# Memory.net
KiCad netlist of a schematic drawn in Altium Designer
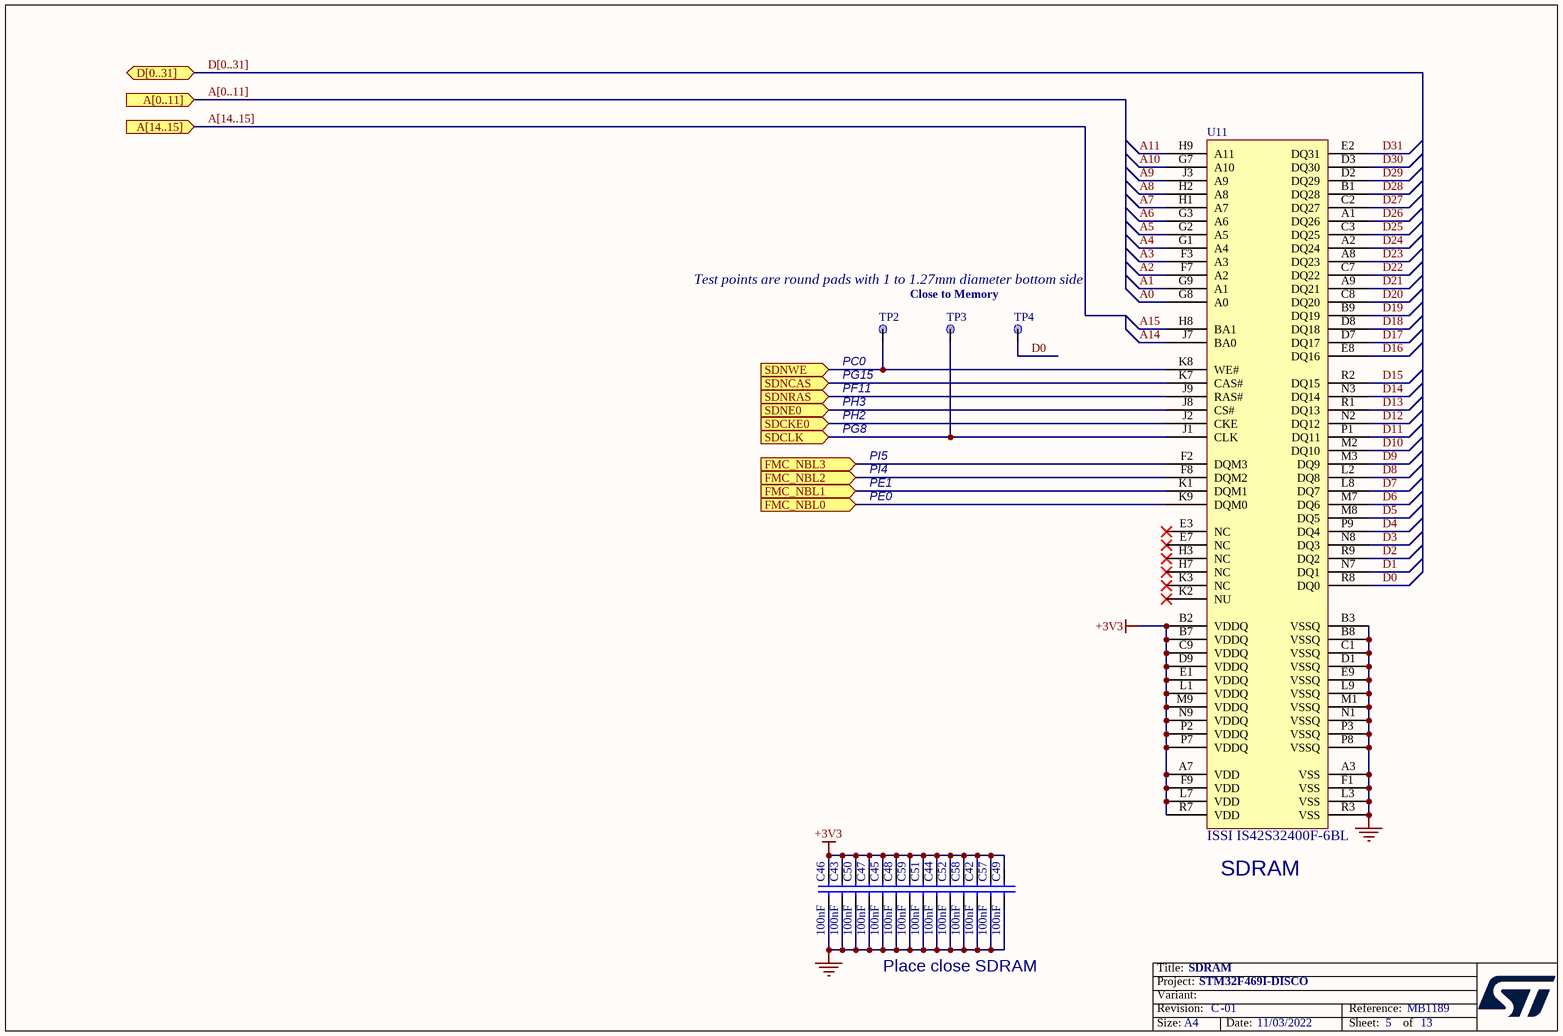
[diagram p0: Memory.SchDoc]

(export (version "E")
  (design (tool "Eeschema 10.0.6"))
  (components
    (comp (ref "C42")
      (value "100nF")
      (footprint "0402C")
      (description "Capacitor")
      (fields (field (name "PUBLISHER") "Altium Limited"))
      (libsource (lib "Miscellaneous Devices") (part "Cap"))
    )
    (comp (ref "C43")
      (value "100nF")
      (footprint "0402C")
      (description "Capacitor")
      (fields (field (name "PUBLISHER") "Altium Limited"))
      (libsource (lib "Miscellaneous Devices") (part "Cap"))
    )
    (comp (ref "C44")
      (value "100nF")
      (footprint "0402C")
      (description "Capacitor")
      (fields (field (name "PUBLISHER") "Altium Limited"))
      (libsource (lib "Miscellaneous Devices") (part "Cap"))
    )
    (comp (ref "C45")
      (value "100nF")
      (footprint "0402C")
      (description "Capacitor")
      (fields (field (name "PUBLISHER") "Altium Limited"))
      (libsource (lib "Miscellaneous Devices") (part "Cap"))
    )
    (comp (ref "C46")
      (value "100nF")
      (footprint "0402C")
      (description "Capacitor")
      (fields (field (name "PUBLISHER") "Altium Limited"))
      (libsource (lib "Miscellaneous Devices") (part "Cap"))
    )
    (comp (ref "C47")
      (value "100nF")
      (footprint "0402C")
      (description "Capacitor")
      (fields (field (name "PUBLISHER") "Altium Limited"))
      (libsource (lib "Miscellaneous Devices") (part "Cap"))
    )
    (comp (ref "C48")
      (value "100nF")
      (footprint "0402C")
      (description "Capacitor")
      (fields (field (name "PUBLISHER") "Altium Limited"))
      (libsource (lib "Miscellaneous Devices") (part "Cap"))
    )
    (comp (ref "C49")
      (value "100nF")
      (footprint "0402C")
      (description "Capacitor")
      (fields (field (name "PUBLISHER") "Altium Limited"))
      (libsource (lib "Miscellaneous Devices") (part "Cap"))
    )
    (comp (ref "C50")
      (value "100nF")
      (footprint "0402C")
      (description "Capacitor")
      (fields (field (name "PUBLISHER") "Altium Limited"))
      (libsource (lib "Miscellaneous Devices") (part "Cap"))
    )
    (comp (ref "C51")
      (value "100nF")
      (footprint "0402C")
      (description "Capacitor")
      (fields (field (name "PUBLISHER") "Altium Limited"))
      (libsource (lib "Miscellaneous Devices") (part "Cap"))
    )
    (comp (ref "C52")
      (value "100nF")
      (footprint "0402C")
      (description "Capacitor")
      (fields (field (name "PUBLISHER") "Altium Limited"))
      (libsource (lib "Miscellaneous Devices") (part "Cap"))
    )
    (comp (ref "C57")
      (value "100nF")
      (footprint "0402C")
      (description "Capacitor")
      (fields (field (name "PUBLISHER") "Altium Limited"))
      (libsource (lib "Miscellaneous Devices") (part "Cap"))
    )
    (comp (ref "C58")
      (value "100nF")
      (footprint "0402C")
      (description "Capacitor")
      (fields (field (name "PUBLISHER") "Altium Limited"))
      (libsource (lib "Miscellaneous Devices") (part "Cap"))
    )
    (comp (ref "C59")
      (value "100nF")
      (footprint "0402C")
      (description "Capacitor")
      (fields (field (name "PUBLISHER") "Altium Limited"))
      (libsource (lib "Miscellaneous Devices") (part "Cap"))
    )
    (comp (ref "TP2") (value "TP") (footprint "TP_C40") (libsource (lib "Almos") (part "TP")))
    (comp (ref "TP3") (value "TP") (footprint "TP_C40") (libsource (lib "Almos") (part "TP")))
    (comp (ref "TP4") (value "TP") (footprint "TP_C40") (libsource (lib "Almos") (part "TP")))
    (comp (ref "U11")
      (value "ISSI IS42S32400F-6BL")
      (footprint "ICC_VFBGA90_8X13_P080")
      (description "SDRAM 128MBit 166MHZ 90BGA")
      (libsource (lib "MB1189") (part "IS42S32400F-6BL"))
    )
  )
  (nets
    (net (code "1") (name "+3V3") (class "Default")
      (node (ref "C42") (pin "1") (pinfunction "1_1") (pintype "passive"))
      (node (ref "C43") (pin "1") (pinfunction "1_1") (pintype "passive"))
      (node (ref "C44") (pin "1") (pinfunction "1_1") (pintype "passive"))
      (node (ref "C45") (pin "1") (pinfunction "1_1") (pintype "passive"))
      (node (ref "C46") (pin "1") (pinfunction "1_1") (pintype "passive"))
      (node (ref "C47") (pin "1") (pinfunction "1_1") (pintype "passive"))
      (node (ref "C48") (pin "1") (pinfunction "1_1") (pintype "passive"))
      (node (ref "C49") (pin "1") (pinfunction "1_1") (pintype "passive"))
      (node (ref "C50") (pin "1") (pinfunction "1_1") (pintype "passive"))
      (node (ref "C51") (pin "1") (pinfunction "1_1") (pintype "passive"))
      (node (ref "C52") (pin "1") (pinfunction "1_1") (pintype "passive"))
      (node (ref "C57") (pin "1") (pinfunction "1_1") (pintype "passive"))
      (node (ref "C58") (pin "1") (pinfunction "1_1") (pintype "passive"))
      (node (ref "C59") (pin "1") (pinfunction "1_1") (pintype "passive"))
      (node (ref "U11") (pin "A7") (pinfunction "VDD_A7") (pintype "passive"))
      (node (ref "U11") (pin "B2") (pinfunction "VDDQ_B2") (pintype "passive"))
      (node (ref "U11") (pin "B7") (pinfunction "VDDQ_B7") (pintype "passive"))
      (node (ref "U11") (pin "C9") (pinfunction "VDDQ_C9") (pintype "passive"))
      (node (ref "U11") (pin "D9") (pinfunction "VDDQ_D9") (pintype "passive"))
      (node (ref "U11") (pin "E1") (pinfunction "VDDQ_E1") (pintype "passive"))
      (node (ref "U11") (pin "F9") (pinfunction "VDD_F9") (pintype "passive"))
      (node (ref "U11") (pin "L1") (pinfunction "VDDQ_L1") (pintype "passive"))
      (node (ref "U11") (pin "L7") (pinfunction "VDD_L7") (pintype "passive"))
      (node (ref "U11") (pin "M9") (pinfunction "VDDQ_M9") (pintype "passive"))
      (node (ref "U11") (pin "N9") (pinfunction "VDDQ_N9") (pintype "passive"))
      (node (ref "U11") (pin "P2") (pinfunction "VDDQ_P2") (pintype "passive"))
      (node (ref "U11") (pin "P7") (pinfunction "VDDQ_P7") (pintype "passive"))
      (node (ref "U11") (pin "R7") (pinfunction "VDD_R7") (pintype "passive"))
    )
    (net (code "2") (name "/A0") (class "Default")
      (node (ref "U11") (pin "G8") (pinfunction "A0_G8") (pintype "passive"))
    )
    (net (code "3") (name "/A1") (class "Default")
      (node (ref "U11") (pin "G9") (pinfunction "A1_G9") (pintype "passive"))
    )
    (net (code "4") (name "/A2") (class "Default")
      (node (ref "U11") (pin "F7") (pinfunction "A2_F7") (pintype "passive"))
    )
    (net (code "5") (name "/A3") (class "Default")
      (node (ref "U11") (pin "F3") (pinfunction "A3_F3") (pintype "passive"))
    )
    (net (code "6") (name "/A4") (class "Default")
      (node (ref "U11") (pin "G1") (pinfunction "A4_G1") (pintype "passive"))
    )
    (net (code "7") (name "/A5") (class "Default")
      (node (ref "U11") (pin "G2") (pinfunction "A5_G2") (pintype "passive"))
    )
    (net (code "8") (name "/A6") (class "Default")
      (node (ref "U11") (pin "G3") (pinfunction "A6_G3") (pintype "passive"))
    )
    (net (code "9") (name "/A7") (class "Default")
      (node (ref "U11") (pin "H1") (pinfunction "A7_H1") (pintype "passive"))
    )
    (net (code "10") (name "/A8") (class "Default")
      (node (ref "U11") (pin "H2") (pinfunction "A8_H2") (pintype "passive"))
    )
    (net (code "11") (name "/A9") (class "Default")
      (node (ref "U11") (pin "J3") (pinfunction "A9_J3") (pintype "passive"))
    )
    (net (code "12") (name "/A10") (class "Default")
      (node (ref "U11") (pin "G7") (pinfunction "A10_G7") (pintype "passive"))
    )
    (net (code "13") (name "/A11") (class "Default")
      (node (ref "U11") (pin "H9") (pinfunction "A11_H9") (pintype "passive"))
    )
    (net (code "14") (name "/A14") (class "Default")
      (node (ref "U11") (pin "J7") (pinfunction "BA0_J7") (pintype "passive"))
    )
    (net (code "15") (name "/A15") (class "Default")
      (node (ref "U11") (pin "H8") (pinfunction "BA1_H8") (pintype "passive"))
    )
    (net (code "18") (name "/D0") (class "Default")
      (node (ref "TP4") (pin "1") (pinfunction "1_1") (pintype "passive"))
      (node (ref "U11") (pin "R8") (pinfunction "DQ0_R8") (pintype "passive"))
    )
    (net (code "19") (name "/D1") (class "Default")
      (node (ref "U11") (pin "N7") (pinfunction "DQ1_N7") (pintype "passive"))
    )
    (net (code "20") (name "/D2") (class "Default")
      (node (ref "U11") (pin "R9") (pinfunction "DQ2_R9") (pintype "passive"))
    )
    (net (code "21") (name "/D3") (class "Default")
      (node (ref "U11") (pin "N8") (pinfunction "DQ3_N8") (pintype "passive"))
    )
    (net (code "22") (name "/D4") (class "Default")
      (node (ref "U11") (pin "P9") (pinfunction "DQ4_P9") (pintype "passive"))
    )
    (net (code "23") (name "/D5") (class "Default")
      (node (ref "U11") (pin "M8") (pinfunction "DQ5_M8") (pintype "passive"))
    )
    (net (code "24") (name "/D6") (class "Default")
      (node (ref "U11") (pin "M7") (pinfunction "DQ6_M7") (pintype "passive"))
    )
    (net (code "25") (name "/D7") (class "Default")
      (node (ref "U11") (pin "L8") (pinfunction "DQ7_L8") (pintype "passive"))
    )
    (net (code "26") (name "/D8") (class "Default")
      (node (ref "U11") (pin "L2") (pinfunction "DQ8_L2") (pintype "passive"))
    )
    (net (code "27") (name "/D9") (class "Default")
      (node (ref "U11") (pin "M3") (pinfunction "DQ9_M3") (pintype "passive"))
    )
    (net (code "28") (name "/D10") (class "Default")
      (node (ref "U11") (pin "M2") (pinfunction "DQ10_M2") (pintype "passive"))
    )
    (net (code "29") (name "/D11") (class "Default")
      (node (ref "U11") (pin "P1") (pinfunction "DQ11_P1") (pintype "passive"))
    )
    (net (code "30") (name "/D12") (class "Default")
      (node (ref "U11") (pin "N2") (pinfunction "DQ12_N2") (pintype "passive"))
    )
    (net (code "31") (name "/D13") (class "Default")
      (node (ref "U11") (pin "R1") (pinfunction "DQ13_R1") (pintype "passive"))
    )
    (net (code "32") (name "/D14") (class "Default")
      (node (ref "U11") (pin "N3") (pinfunction "DQ14_N3") (pintype "passive"))
    )
    (net (code "33") (name "/D15") (class "Default")
      (node (ref "U11") (pin "R2") (pinfunction "DQ15_R2") (pintype "passive"))
    )
    (net (code "34") (name "/D16") (class "Default")
      (node (ref "U11") (pin "E8") (pinfunction "DQ16_E8") (pintype "passive"))
    )
    (net (code "35") (name "/D17") (class "Default")
      (node (ref "U11") (pin "D7") (pinfunction "DQ17_D7") (pintype "passive"))
    )
    (net (code "36") (name "/D18") (class "Default")
      (node (ref "U11") (pin "D8") (pinfunction "DQ18_D8") (pintype "passive"))
    )
    (net (code "37") (name "/D19") (class "Default")
      (node (ref "U11") (pin "B9") (pinfunction "DQ19_B9") (pintype "passive"))
    )
    (net (code "38") (name "/D20") (class "Default")
      (node (ref "U11") (pin "C8") (pinfunction "DQ20_C8") (pintype "passive"))
    )
    (net (code "39") (name "/D21") (class "Default")
      (node (ref "U11") (pin "A9") (pinfunction "DQ21_A9") (pintype "passive"))
    )
    (net (code "40") (name "/D22") (class "Default")
      (node (ref "U11") (pin "C7") (pinfunction "DQ22_C7") (pintype "passive"))
    )
    (net (code "41") (name "/D23") (class "Default")
      (node (ref "U11") (pin "A8") (pinfunction "DQ23_A8") (pintype "passive"))
    )
    (net (code "42") (name "/D24") (class "Default")
      (node (ref "U11") (pin "A2") (pinfunction "DQ24_A2") (pintype "passive"))
    )
    (net (code "43") (name "/D25") (class "Default")
      (node (ref "U11") (pin "C3") (pinfunction "DQ25_C3") (pintype "passive"))
    )
    (net (code "44") (name "/D26") (class "Default")
      (node (ref "U11") (pin "A1") (pinfunction "DQ26_A1") (pintype "passive"))
    )
    (net (code "45") (name "/D27") (class "Default")
      (node (ref "U11") (pin "C2") (pinfunction "DQ27_C2") (pintype "passive"))
    )
    (net (code "46") (name "/D28") (class "Default")
      (node (ref "U11") (pin "B1") (pinfunction "DQ28_B1") (pintype "passive"))
    )
    (net (code "47") (name "/D29") (class "Default")
      (node (ref "U11") (pin "D2") (pinfunction "DQ29_D2") (pintype "passive"))
    )
    (net (code "48") (name "/D30") (class "Default")
      (node (ref "U11") (pin "D3") (pinfunction "DQ30_D3") (pintype "passive"))
    )
    (net (code "49") (name "/D31") (class "Default")
      (node (ref "U11") (pin "E2") (pinfunction "DQ31_E2") (pintype "passive"))
    )
    (net (code "51") (name "/FMC_NBL0") (class "Default")
      (node (ref "U11") (pin "K9") (pinfunction "DQM0_K9") (pintype "passive"))
    )
    (net (code "52") (name "/FMC_NBL1") (class "Default")
      (node (ref "U11") (pin "K1") (pinfunction "DQM1_K1") (pintype "passive"))
    )
    (net (code "53") (name "/FMC_NBL2") (class "Default")
      (node (ref "U11") (pin "F8") (pinfunction "DQM2_F8") (pintype "passive"))
    )
    (net (code "54") (name "/FMC_NBL3") (class "Default")
      (node (ref "U11") (pin "F2") (pinfunction "DQM3_F2") (pintype "passive"))
    )
    (net (code "55") (name "/SDCKE0") (class "Default")
      (node (ref "U11") (pin "J2") (pinfunction "CKE_J2") (pintype "passive"))
    )
    (net (code "56") (name "/SDCLK") (class "Default")
      (node (ref "TP3") (pin "1") (pinfunction "1_1") (pintype "passive"))
      (node (ref "U11") (pin "J1") (pinfunction "CLK_J1") (pintype "passive"))
    )
    (net (code "57") (name "/SDNCAS") (class "Default")
      (node (ref "U11") (pin "K7") (pinfunction "CAS#_K7") (pintype "passive"))
    )
    (net (code "58") (name "/SDNE0") (class "Default")
      (node (ref "U11") (pin "J8") (pinfunction "CS#_J8") (pintype "passive"))
    )
    (net (code "59") (name "/SDNRAS") (class "Default")
      (node (ref "U11") (pin "J9") (pinfunction "RAS#_J9") (pintype "passive"))
    )
    (net (code "60") (name "/SDNWE") (class "Default")
      (node (ref "TP2") (pin "1") (pinfunction "1_1") (pintype "passive"))
      (node (ref "U11") (pin "K8") (pinfunction "WE#_K8") (pintype "passive"))
    )
    (net (code "61") (name "GND") (class "Default")
      (node (ref "C42") (pin "2") (pinfunction "2_2") (pintype "passive"))
      (node (ref "C43") (pin "2") (pinfunction "2_2") (pintype "passive"))
      (node (ref "C44") (pin "2") (pinfunction "2_2") (pintype "passive"))
      (node (ref "C45") (pin "2") (pinfunction "2_2") (pintype "passive"))
      (node (ref "C46") (pin "2") (pinfunction "2_2") (pintype "passive"))
      (node (ref "C47") (pin "2") (pinfunction "2_2") (pintype "passive"))
      (node (ref "C48") (pin "2") (pinfunction "2_2") (pintype "passive"))
      (node (ref "C49") (pin "2") (pinfunction "2_2") (pintype "passive"))
      (node (ref "C50") (pin "2") (pinfunction "2_2") (pintype "passive"))
      (node (ref "C51") (pin "2") (pinfunction "2_2") (pintype "passive"))
      (node (ref "C52") (pin "2") (pinfunction "2_2") (pintype "passive"))
      (node (ref "C57") (pin "2") (pinfunction "2_2") (pintype "passive"))
      (node (ref "C58") (pin "2") (pinfunction "2_2") (pintype "passive"))
      (node (ref "C59") (pin "2") (pinfunction "2_2") (pintype "passive"))
      (node (ref "U11") (pin "A3") (pinfunction "VSS_A3") (pintype "passive"))
      (node (ref "U11") (pin "B3") (pinfunction "VSSQ_B3") (pintype "passive"))
      (node (ref "U11") (pin "B8") (pinfunction "VSSQ_B8") (pintype "passive"))
      (node (ref "U11") (pin "C1") (pinfunction "VSSQ_C1") (pintype "passive"))
      (node (ref "U11") (pin "D1") (pinfunction "VSSQ_D1") (pintype "passive"))
      (node (ref "U11") (pin "E9") (pinfunction "VSSQ_E9") (pintype "passive"))
      (node (ref "U11") (pin "F1") (pinfunction "VSS_F1") (pintype "passive"))
      (node (ref "U11") (pin "L3") (pinfunction "VSS_L3") (pintype "passive"))
      (node (ref "U11") (pin "L9") (pinfunction "VSSQ_L9") (pintype "passive"))
      (node (ref "U11") (pin "M1") (pinfunction "VSSQ_M1") (pintype "passive"))
      (node (ref "U11") (pin "N1") (pinfunction "VSSQ_N1") (pintype "passive"))
      (node (ref "U11") (pin "P3") (pinfunction "VSSQ_P3") (pintype "passive"))
      (node (ref "U11") (pin "P8") (pinfunction "VSSQ_P8") (pintype "passive"))
      (node (ref "U11") (pin "R3") (pinfunction "VSS_R3") (pintype "passive"))
    )
    (net (code "62") (name "unconnected-(U11-NC-PadE3)") (class "Default")
      (node (ref "U11") (pin "E3") (pinfunction "NC_E3") (pintype "passive+no_connect"))
    )
    (net (code "63") (name "unconnected-(U11-NC-PadE7)") (class "Default")
      (node (ref "U11") (pin "E7") (pinfunction "NC_E7") (pintype "passive+no_connect"))
    )
    (net (code "64") (name "unconnected-(U11-NC-PadH3)") (class "Default")
      (node (ref "U11") (pin "H3") (pinfunction "NC_H3") (pintype "passive+no_connect"))
    )
    (net (code "65") (name "unconnected-(U11-NC-PadH7)") (class "Default")
      (node (ref "U11") (pin "H7") (pinfunction "NC_H7") (pintype "passive+no_connect"))
    )
    (net (code "66") (name "unconnected-(U11-NC-PadK3)") (class "Default")
      (node (ref "U11") (pin "K3") (pinfunction "NC_K3") (pintype "passive+no_connect"))
    )
    (net (code "67") (name "unconnected-(U11-NU-PadK2)") (class "Default")
      (node (ref "U11") (pin "K2") (pinfunction "NU_K2") (pintype "passive+no_connect"))
    )
  )
)
